# biolab_rev2.net
KiCad netlist of a schematic drawn in Altium Designer
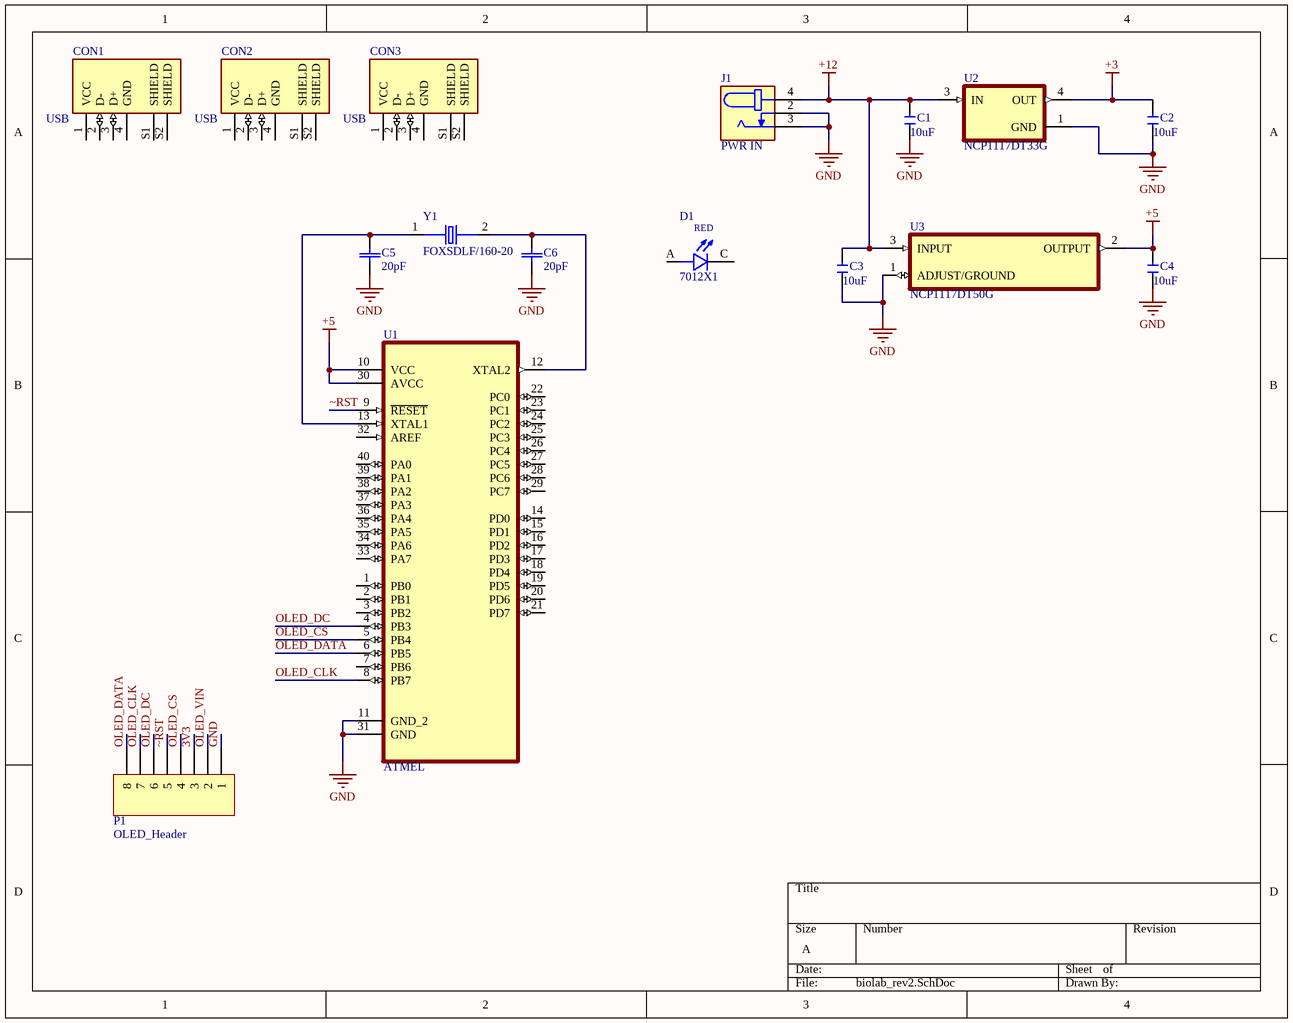
[diagram p0: biolab_rev2.SchDoc]

(export (version "E")
  (design (tool "Eeschema 10.0.6"))
  (components
    (comp (ref "C1")
      (value "10uF")
      (footprint "C0603")
      (description "302010103")
      (fields
        (field (name "MP") "CERAMIC-10UF-10V-10%-X5R(0603)")
        (field (name "MF") "{'manufacturer': u'Yageo'}")
      )
      (libsource (lib "SnapEDA_Library") (part "CERAMIC-10UF-10V-10%-X5R(0603)"))
    )
    (comp (ref "C2")
      (value "10uF")
      (footprint "C0603")
      (description "302010103")
      (fields
        (field (name "MP") "CERAMIC-10UF-10V-10%-X5R(0603)")
        (field (name "MF") "{'manufacturer': u'Yageo'}")
      )
      (libsource (lib "SnapEDA_Library") (part "CERAMIC-10UF-10V-10%-X5R(0603)"))
    )
    (comp (ref "C3")
      (value "10uF")
      (footprint "C0603")
      (description "302010103")
      (fields
        (field (name "MP") "CERAMIC-10UF-10V-10%-X5R(0603)")
        (field (name "MF") "{'manufacturer': u'Yageo'}")
      )
      (libsource (lib "SnapEDA_Library") (part "CERAMIC-10UF-10V-10%-X5R(0603)"))
    )
    (comp (ref "C4")
      (value "10uF")
      (footprint "C0603")
      (description "302010103")
      (fields
        (field (name "MP") "CERAMIC-10UF-10V-10%-X5R(0603)")
        (field (name "MF") "{'manufacturer': u'Yageo'}")
      )
      (libsource (lib "SnapEDA_Library") (part "CERAMIC-10UF-10V-10%-X5R(0603)"))
    )
    (comp (ref "C5")
      (value "20pF")
      (footprint "CAPC1608X85N")
      (description "CAPACITOR, 0603")
      (fields (field (name "MP") "C0603C200J5GACTU") (field (name "MF") "{'manufacturer': u'KEMET'}"))
      (libsource (lib "SnapEDA_Library") (part "C0603C200J5GACTU"))
    )
    (comp (ref "C6")
      (value "20pF")
      (footprint "CAPC1608X85N")
      (description "CAPACITOR, 0603")
      (fields (field (name "MP") "C0603C200J5GACTU") (field (name "MF") "{'manufacturer': u'KEMET'}"))
      (libsource (lib "SnapEDA_Library") (part "C0603C200J5GACTU"))
    )
    (comp (ref "CON1")
      (value "USB")
      (footprint "GCT_USB1130-15-A_REVA")
      (fields
        (field (name "MP") "USB1130-15-A_REVA")
        (field (name "MF") "{'manufacturer': u'Global Connector Technology'}")
      )
      (libsource (lib "SnapEDA_Library") (part "USB1130-15-A_REVA"))
    )
    (comp (ref "CON2")
      (value "USB")
      (footprint "GCT_USB1130-15-A_REVA")
      (fields
        (field (name "MP") "USB1130-15-A_REVA")
        (field (name "MF") "{'manufacturer': u'Global Connector Technology'}")
      )
      (libsource (lib "SnapEDA_Library") (part "USB1130-15-A_REVA"))
    )
    (comp (ref "CON3")
      (value "USB")
      (footprint "GCT_USB1130-15-A_REVA")
      (fields
        (field (name "MP") "USB1130-15-A_REVA")
        (field (name "MF") "{'manufacturer': u'Global Connector Technology'}")
      )
      (libsource (lib "SnapEDA_Library") (part "USB1130-15-A_REVA"))
    )
    (comp (ref "D1")
      (value "7012X1")
      (footprint "LED_7012X1")
      (description "Red LED Indication - Discrete 1.7V 0805 (2012 Metric)")
      (fields (field (name "MF") "{'manufacturer': u'Visual'}"))
      (libsource (lib "SnapEDA_Library") (part "7012X1"))
    )
    (comp (ref "J1")
      (value "PWR IN")
      (footprint "NINIGI_DC-005")
      (description "DC Jack")
      (fields (field (name "MP") "DC-005") (field (name "MF") "{'manufacturer': u'Best Inc.'}"))
      (libsource (lib "SnapEDA_Library") (part "DC-005"))
    )
    (comp (ref "P1")
      (value "OLED_Header")
      (footprint "HDR1X8")
      (description "Header, 8-Pin")
      (fields (field (name "PUBLISHER") "Altium Limited"))
      (libsource (lib "Miscellaneous Connectors") (part "Header 8"))
    )
    (comp (ref "U1")
      (value "ATMEL")
      (footprint "DIP254P1524X483-40")
      (description "8-bit Microcontroller with In-System Programmable  Flash")
      (fields
        (field (name "MP") "ATMEGA644PV-10PU")
        (field (name "MF") "{'manufacturer': u'Microchip Technology'}")
      )
      (libsource (lib "SnapEDA_Library") (part "ATMEGA644PV-10PU"))
    )
    (comp (ref "U2")
      (value "NCP1117DT33G")
      (footprint "VREG_NCP1117DT33G")
      (description "1.0 A Positive LDO Linear Voltage Regulator (Fixed and Adjustable) Vout: 3.3 V")
      (fields (field (name "MF") "{'manufacturer': u'ON Semiconductor'}"))
      (libsource (lib "SnapEDA_Library") (part "NCP1117DT33G"))
    )
    (comp (ref "U3")
      (value "NCP1117DT50G")
      (footprint "DPAK229P990X238-4N")
      (fields (field (name "MF") "{'manufacturer': u'ON Semiconductor'}"))
      (libsource (lib "SnapEDA_Library") (part "NCP1117DT50G"))
    )
    (comp (ref "Y1")
      (value "FOXSDLF/160-20")
      (footprint "XTAL_FOXSDLF/160-20")
      (description "Crystal 16MHz 20pF 2-Pin HC-49/SD")
      (fields (field (name "MF") "{'manufacturer': u'Fox Electronics'}"))
      (libsource (lib "SnapEDA_Library") (part "FOXSDLF/160-20"))
    )
  )
  (nets
    (net (code "1") (name "+3") (class "Default")
      (node (ref "C2") (pin "2") (pinfunction "2_2") (pintype "passive"))
      (node (ref "U2") (pin "4") (pinfunction "OUT_4") (pintype "output"))
    )
    (net (code "2") (name "+5") (class "Default")
      (node (ref "C4") (pin "2") (pinfunction "2_2") (pintype "passive"))
      (node (ref "U1") (pin "10") (pinfunction "VCC_10") (pintype "power_in"))
      (node (ref "U1") (pin "30") (pinfunction "AVCC_30") (pintype "power_in"))
      (node (ref "U3") (pin "2") (pinfunction "OUTPUT_2") (pintype "output"))
    )
    (net (code "3") (name "+12") (class "Default")
      (node (ref "C1") (pin "2") (pinfunction "2_2") (pintype "passive"))
      (node (ref "C3") (pin "2") (pinfunction "2_2") (pintype "passive"))
      (node (ref "J1") (pin "4") (pinfunction "2_4") (pintype "passive"))
      (node (ref "U2") (pin "3") (pinfunction "IN_3") (pintype "input"))
      (node (ref "U3") (pin "3") (pinfunction "INPUT_3") (pintype "input"))
    )
    (net (code "4") (name "/3V3") (class "Default")
      (node (ref "P1") (pin "3") (pinfunction "3_3") (pintype "passive"))
    )
    (net (code "5") (name "/OLED_CLK") (class "Default")
      (node (ref "P1") (pin "7") (pinfunction "7_7") (pintype "passive"))
      (node (ref "U1") (pin "8") (pinfunction "PB7_8") (pintype "bidirectional"))
    )
    (net (code "6") (name "/OLED_CS") (class "Default")
      (node (ref "P1") (pin "4") (pinfunction "4_4") (pintype "passive"))
      (node (ref "U1") (pin "5") (pinfunction "PB4_5") (pintype "bidirectional"))
    )
    (net (code "7") (name "/OLED_DATA") (class "Default")
      (node (ref "P1") (pin "8") (pinfunction "8_8") (pintype "passive"))
      (node (ref "U1") (pin "6") (pinfunction "PB5_6") (pintype "bidirectional"))
    )
    (net (code "8") (name "/OLED_DC") (class "Default")
      (node (ref "P1") (pin "6") (pinfunction "6_6") (pintype "passive"))
      (node (ref "U1") (pin "4") (pinfunction "PB3_4") (pintype "bidirectional"))
    )
    (net (code "9") (name "/OLED_VIN") (class "Default")
      (node (ref "P1") (pin "2") (pinfunction "2_2") (pintype "passive"))
    )
    (net (code "10") (name "/~RST") (class "Default")
      (node (ref "P1") (pin "5") (pinfunction "5_5") (pintype "passive"))
      (node (ref "U1") (pin "9") (pinfunction "~{RESET}_9") (pintype "input"))
    )
    (net (code "11") (name "GND") (class "Default")
      (node (ref "C1") (pin "1") (pinfunction "1_1") (pintype "passive"))
      (node (ref "C2") (pin "1") (pinfunction "1_1") (pintype "passive"))
      (node (ref "C3") (pin "1") (pinfunction "1_1") (pintype "passive"))
      (node (ref "C4") (pin "1") (pinfunction "1_1") (pintype "passive"))
      (node (ref "C5") (pin "1") (pinfunction "C1_1") (pintype "passive"))
      (node (ref "C6") (pin "1") (pinfunction "C1_1") (pintype "passive"))
      (node (ref "J1") (pin "2") (pinfunction "4_2") (pintype "passive"))
      (node (ref "J1") (pin "3") (pinfunction "5_3") (pintype "passive"))
      (node (ref "P1") (pin "1") (pinfunction "1_1") (pintype "passive"))
      (node (ref "U1") (pin "11") (pinfunction "GND_2_11") (pintype "passive"))
      (node (ref "U1") (pin "31") (pinfunction "GND_31") (pintype "passive"))
      (node (ref "U2") (pin "1") (pinfunction "GND_1") (pintype "power_in"))
      (node (ref "U3") (pin "1") (pinfunction "ADJUST/GROUND_1") (pintype "bidirectional"))
    )
    (net (code "12") (name "Net-(C5-C2)") (class "Default")
      (node (ref "C5") (pin "2") (pinfunction "C2_2") (pintype "passive"))
      (node (ref "U1") (pin "13") (pinfunction "XTAL1_13") (pintype "input"))
      (node (ref "Y1") (pin "1") (pinfunction "1_1") (pintype "passive"))
    )
    (net (code "13") (name "Net-(C6-C2)") (class "Default")
      (node (ref "C6") (pin "2") (pinfunction "C2_2") (pintype "passive"))
      (node (ref "U1") (pin "12") (pinfunction "XTAL2_12") (pintype "output"))
      (node (ref "Y1") (pin "2") (pinfunction "2_2") (pintype "passive"))
    )
    (net (code "14") (name "unconnected-(CON1-D+-Pad3)") (class "Default")
      (node (ref "CON1") (pin "3") (pinfunction "D+_3") (pintype "bidirectional"))
    )
    (net (code "15") (name "unconnected-(CON1-D--Pad2)") (class "Default")
      (node (ref "CON1") (pin "2") (pinfunction "D-_2") (pintype "bidirectional"))
    )
    (net (code "16") (name "unconnected-(CON1-GND-Pad4)") (class "Default")
      (node (ref "CON1") (pin "4") (pinfunction "GND_4") (pintype "power_in"))
    )
    (net (code "17") (name "unconnected-(CON1-SHIELD-PadS1)") (class "Default")
      (node (ref "CON1") (pin "S1") (pinfunction "SHIELD_S1") (pintype "passive"))
    )
    (net (code "18") (name "unconnected-(CON1-SHIELD-PadS2)") (class "Default")
      (node (ref "CON1") (pin "S2") (pinfunction "SHIELD_S2") (pintype "passive"))
    )
    (net (code "19") (name "unconnected-(CON1-VCC-Pad1)") (class "Default")
      (node (ref "CON1") (pin "1") (pinfunction "VCC_1") (pintype "power_in"))
    )
    (net (code "20") (name "unconnected-(CON2-D+-Pad3)") (class "Default")
      (node (ref "CON2") (pin "3") (pinfunction "D+_3") (pintype "bidirectional"))
    )
    (net (code "21") (name "unconnected-(CON2-D--Pad2)") (class "Default")
      (node (ref "CON2") (pin "2") (pinfunction "D-_2") (pintype "bidirectional"))
    )
    (net (code "22") (name "unconnected-(CON2-GND-Pad4)") (class "Default")
      (node (ref "CON2") (pin "4") (pinfunction "GND_4") (pintype "power_in"))
    )
    (net (code "23") (name "unconnected-(CON2-SHIELD-PadS1)") (class "Default")
      (node (ref "CON2") (pin "S1") (pinfunction "SHIELD_S1") (pintype "passive"))
    )
    (net (code "24") (name "unconnected-(CON2-SHIELD-PadS2)") (class "Default")
      (node (ref "CON2") (pin "S2") (pinfunction "SHIELD_S2") (pintype "passive"))
    )
    (net (code "25") (name "unconnected-(CON2-VCC-Pad1)") (class "Default")
      (node (ref "CON2") (pin "1") (pinfunction "VCC_1") (pintype "power_in"))
    )
    (net (code "26") (name "unconnected-(CON3-D+-Pad3)") (class "Default")
      (node (ref "CON3") (pin "3") (pinfunction "D+_3") (pintype "bidirectional"))
    )
    (net (code "27") (name "unconnected-(CON3-D--Pad2)") (class "Default")
      (node (ref "CON3") (pin "2") (pinfunction "D-_2") (pintype "bidirectional"))
    )
    (net (code "28") (name "unconnected-(CON3-GND-Pad4)") (class "Default")
      (node (ref "CON3") (pin "4") (pinfunction "GND_4") (pintype "power_in"))
    )
    (net (code "29") (name "unconnected-(CON3-SHIELD-PadS1)") (class "Default")
      (node (ref "CON3") (pin "S1") (pinfunction "SHIELD_S1") (pintype "passive"))
    )
    (net (code "30") (name "unconnected-(CON3-SHIELD-PadS2)") (class "Default")
      (node (ref "CON3") (pin "S2") (pinfunction "SHIELD_S2") (pintype "passive"))
    )
    (net (code "31") (name "unconnected-(CON3-VCC-Pad1)") (class "Default")
      (node (ref "CON3") (pin "1") (pinfunction "VCC_1") (pintype "power_in"))
    )
    (net (code "32") (name "unconnected-(D1-PadA)") (class "Default")
      (node (ref "D1") (pin "A") (pinfunction "A_A") (pintype "passive"))
    )
    (net (code "33") (name "unconnected-(D1-PadC)") (class "Default")
      (node (ref "D1") (pin "C") (pinfunction "C_C") (pintype "passive"))
    )
    (net (code "34") (name "unconnected-(U1-AREF-Pad32)") (class "Default")
      (node (ref "U1") (pin "32") (pinfunction "AREF_32") (pintype "input"))
    )
    (net (code "35") (name "unconnected-(U1-PA0-Pad40)") (class "Default")
      (node (ref "U1") (pin "40") (pinfunction "PA0_40") (pintype "bidirectional"))
    )
    (net (code "36") (name "unconnected-(U1-PA1-Pad39)") (class "Default")
      (node (ref "U1") (pin "39") (pinfunction "PA1_39") (pintype "bidirectional"))
    )
    (net (code "37") (name "unconnected-(U1-PA2-Pad38)") (class "Default")
      (node (ref "U1") (pin "38") (pinfunction "PA2_38") (pintype "bidirectional"))
    )
    (net (code "38") (name "unconnected-(U1-PA3-Pad37)") (class "Default")
      (node (ref "U1") (pin "37") (pinfunction "PA3_37") (pintype "bidirectional"))
    )
    (net (code "39") (name "unconnected-(U1-PA4-Pad36)") (class "Default")
      (node (ref "U1") (pin "36") (pinfunction "PA4_36") (pintype "bidirectional"))
    )
    (net (code "40") (name "unconnected-(U1-PA5-Pad35)") (class "Default")
      (node (ref "U1") (pin "35") (pinfunction "PA5_35") (pintype "bidirectional"))
    )
    (net (code "41") (name "unconnected-(U1-PA6-Pad34)") (class "Default")
      (node (ref "U1") (pin "34") (pinfunction "PA6_34") (pintype "bidirectional"))
    )
    (net (code "42") (name "unconnected-(U1-PA7-Pad33)") (class "Default")
      (node (ref "U1") (pin "33") (pinfunction "PA7_33") (pintype "bidirectional"))
    )
    (net (code "43") (name "unconnected-(U1-PB0-Pad1)") (class "Default")
      (node (ref "U1") (pin "1") (pinfunction "PB0_1") (pintype "bidirectional"))
    )
    (net (code "44") (name "unconnected-(U1-PB1-Pad2)") (class "Default")
      (node (ref "U1") (pin "2") (pinfunction "PB1_2") (pintype "bidirectional"))
    )
    (net (code "45") (name "unconnected-(U1-PB2-Pad3)") (class "Default")
      (node (ref "U1") (pin "3") (pinfunction "PB2_3") (pintype "bidirectional"))
    )
    (net (code "46") (name "unconnected-(U1-PB6-Pad7)") (class "Default")
      (node (ref "U1") (pin "7") (pinfunction "PB6_7") (pintype "bidirectional"))
    )
    (net (code "47") (name "unconnected-(U1-PC0-Pad22)") (class "Default")
      (node (ref "U1") (pin "22") (pinfunction "PC0_22") (pintype "bidirectional"))
    )
    (net (code "48") (name "unconnected-(U1-PC1-Pad23)") (class "Default")
      (node (ref "U1") (pin "23") (pinfunction "PC1_23") (pintype "bidirectional"))
    )
    (net (code "49") (name "unconnected-(U1-PC2-Pad24)") (class "Default")
      (node (ref "U1") (pin "24") (pinfunction "PC2_24") (pintype "bidirectional"))
    )
    (net (code "50") (name "unconnected-(U1-PC3-Pad25)") (class "Default")
      (node (ref "U1") (pin "25") (pinfunction "PC3_25") (pintype "bidirectional"))
    )
    (net (code "51") (name "unconnected-(U1-PC4-Pad26)") (class "Default")
      (node (ref "U1") (pin "26") (pinfunction "PC4_26") (pintype "bidirectional"))
    )
    (net (code "52") (name "unconnected-(U1-PC5-Pad27)") (class "Default")
      (node (ref "U1") (pin "27") (pinfunction "PC5_27") (pintype "bidirectional"))
    )
    (net (code "53") (name "unconnected-(U1-PC6-Pad28)") (class "Default")
      (node (ref "U1") (pin "28") (pinfunction "PC6_28") (pintype "bidirectional"))
    )
    (net (code "54") (name "unconnected-(U1-PC7-Pad29)") (class "Default")
      (node (ref "U1") (pin "29") (pinfunction "PC7_29") (pintype "bidirectional"))
    )
    (net (code "55") (name "unconnected-(U1-PD0-Pad14)") (class "Default")
      (node (ref "U1") (pin "14") (pinfunction "PD0_14") (pintype "bidirectional"))
    )
    (net (code "56") (name "unconnected-(U1-PD1-Pad15)") (class "Default")
      (node (ref "U1") (pin "15") (pinfunction "PD1_15") (pintype "bidirectional"))
    )
    (net (code "57") (name "unconnected-(U1-PD2-Pad16)") (class "Default")
      (node (ref "U1") (pin "16") (pinfunction "PD2_16") (pintype "bidirectional"))
    )
    (net (code "58") (name "unconnected-(U1-PD3-Pad17)") (class "Default")
      (node (ref "U1") (pin "17") (pinfunction "PD3_17") (pintype "bidirectional"))
    )
    (net (code "59") (name "unconnected-(U1-PD4-Pad18)") (class "Default")
      (node (ref "U1") (pin "18") (pinfunction "PD4_18") (pintype "bidirectional"))
    )
    (net (code "60") (name "unconnected-(U1-PD5-Pad19)") (class "Default")
      (node (ref "U1") (pin "19") (pinfunction "PD5_19") (pintype "bidirectional"))
    )
    (net (code "61") (name "unconnected-(U1-PD6-Pad20)") (class "Default")
      (node (ref "U1") (pin "20") (pinfunction "PD6_20") (pintype "bidirectional"))
    )
    (net (code "62") (name "unconnected-(U1-PD7-Pad21)") (class "Default")
      (node (ref "U1") (pin "21") (pinfunction "PD7_21") (pintype "bidirectional"))
    )
  )
)
